# Sensor_Board_0x08_Dual_Temperatures_2xDS.net
KiCad netlist of a schematic drawn in EAGLE
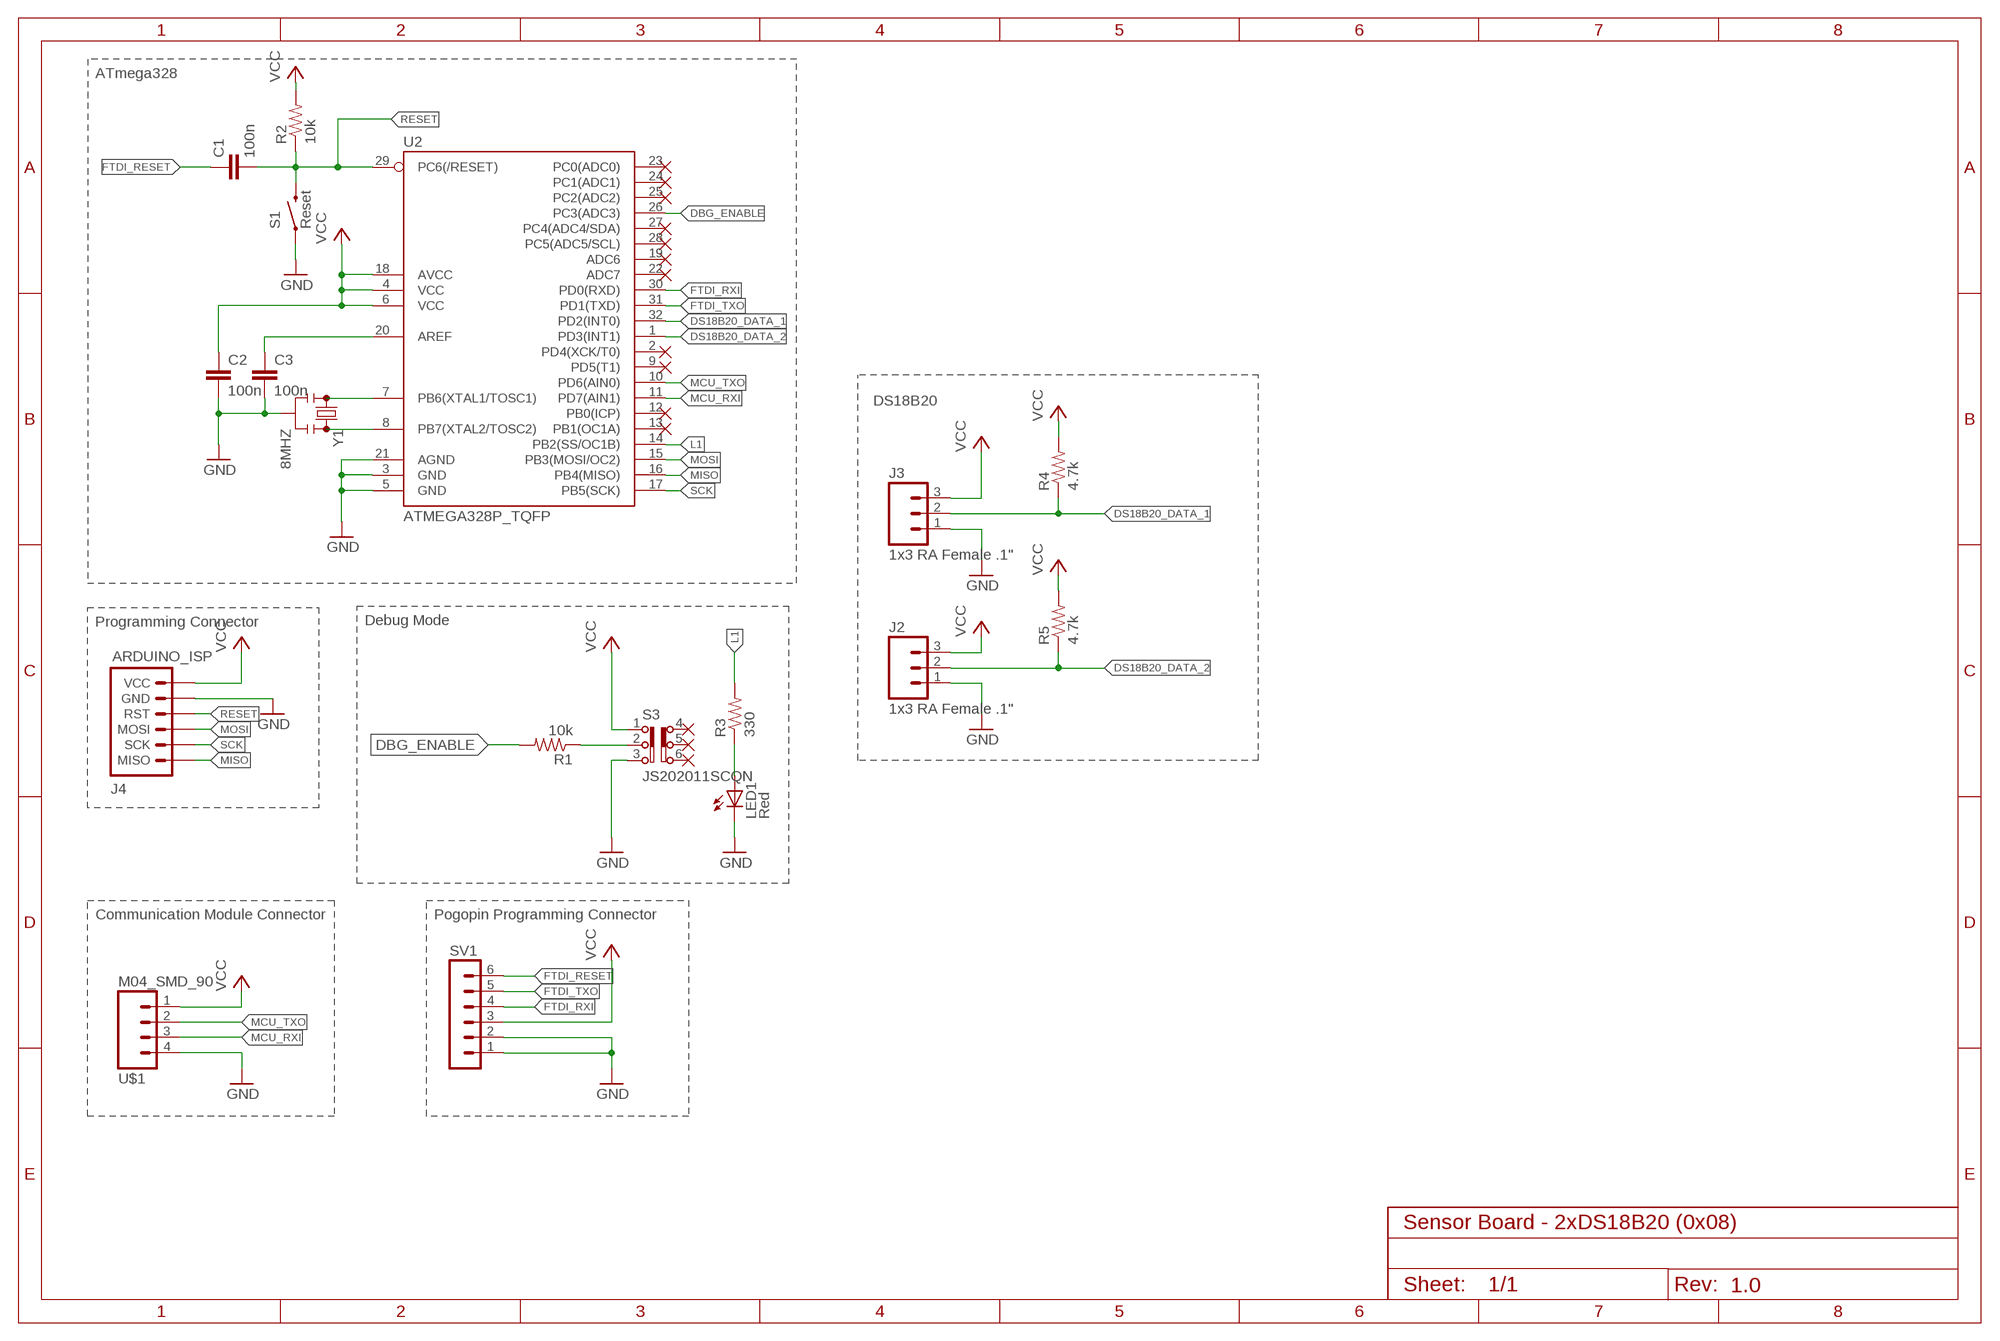
[diagram p0: schematic, sheet 1]

(export (version "E")
  (design (tool "Eeschema 10.0.6"))
  (components
    (comp (ref "C1")
      (value "100n")
      (footprint "eagle-import:C0805")
      (libsource (lib "eagle-import") (part "C"))
    )
    (comp (ref "C2")
      (value "100n")
      (footprint "eagle-import:C0805")
      (libsource (lib "eagle-import") (part "C"))
    )
    (comp (ref "C3")
      (value "100n")
      (footprint "eagle-import:C0805")
      (libsource (lib "eagle-import") (part "C"))
    )
    (comp (ref "J2")
      (value "1x3 RA Female .1\"")
      (footprint "eagle-import:1X03_SMD_RA_FEMALE")
      (libsource (lib "eagle-import") (part "M03SMD_RA_FEMALE"))
    )
    (comp (ref "J3")
      (value "1x3 RA Female .1\"")
      (footprint "eagle-import:1X03_SMD_RA_FEMALE")
      (libsource (lib "eagle-import") (part "M03SMD_RA_FEMALE"))
    )
    (comp (ref "J4")
      (value "ARDUINO_ISP")
      (footprint "eagle-import:M-2X3")
      (libsource (lib "eagle-import") (part "ARDUINO_ISP"))
    )
    (comp (ref "LED1")
      (value "Red")
      (footprint "eagle-import:SML0805")
      (libsource (lib "eagle-import") (part "LEDSML0805"))
    )
    (comp (ref "R1")
      (value "10k")
      (footprint "eagle-import:0805")
      (libsource (lib "eagle-import") (part "RESISTOR0805-RES"))
    )
    (comp (ref "R2")
      (value "10k")
      (footprint "eagle-import:0805")
      (libsource (lib "eagle-import") (part "RESISTOR0805-RES"))
    )
    (comp (ref "R3")
      (value "330")
      (footprint "eagle-import:0805")
      (libsource (lib "eagle-import") (part "RESISTOR0805-RES"))
    )
    (comp (ref "R4")
      (value "4.7k")
      (footprint "eagle-import:0805")
      (libsource (lib "eagle-import") (part "RESISTOR0805-RES"))
    )
    (comp (ref "R5")
      (value "4.7k")
      (footprint "eagle-import:0805")
      (libsource (lib "eagle-import") (part "RESISTOR0805-RES"))
    )
    (comp (ref "S1")
      (value "Reset")
      (footprint "eagle-import:M-PUSHBUTTON-SMD")
      (libsource (lib "eagle-import") (part "PUSHBUTTON"))
    )
    (comp (ref "S3")
      (value "JS202011SCQN")
      (footprint "eagle-import:JS202011SCQN")
      (libsource (lib "eagle-import") (part "JS202011SCQN"))
    )
    (comp (ref "SV1")
      (value "MA06-1")
      (footprint "eagle-import:MA06-1")
      (libsource (lib "eagle-import") (part "MA06-1"))
    )
    (comp (ref "U$1")
      (value "M04_SMD_90")
      (footprint "eagle-import:M04_SMD_90")
      (libsource (lib "eagle-import") (part "M04_SMD_90"))
    )
    (comp (ref "U2")
      (value "ATMEGA328P_TQFP")
      (footprint "eagle-import:TQFP32-08")
      (libsource (lib "eagle-import") (part "ATMEGA328P_TQFP"))
    )
    (comp (ref "Y1")
      (value "8MHZ")
      (footprint "eagle-import:RESONATOR-SMD")
      (libsource (lib "eagle-import") (part "RESONATOR8MHZ"))
    )
  )
  (nets
    (net (code "1") (name "DBG_ENABLE") (class "Default")
      (node (ref "R1") (pin "2") (pinfunction "2_2") (pintype "passive"))
      (node (ref "U2") (pin "26") (pinfunction "PC3(ADC3)_26") (pintype "bidirectional"))
    )
    (net (code "2") (name "DS18B20_DATA_1") (class "Default")
      (node (ref "J3") (pin "2") (pinfunction "2_2") (pintype "passive"))
      (node (ref "R4") (pin "1") (pinfunction "1_1") (pintype "passive"))
      (node (ref "U2") (pin "32") (pinfunction "PD2(INT0)_32") (pintype "bidirectional"))
    )
    (net (code "3") (name "DS18B20_DATA_2") (class "Default")
      (node (ref "J2") (pin "2") (pinfunction "2_2") (pintype "passive"))
      (node (ref "R5") (pin "1") (pinfunction "1_1") (pintype "passive"))
      (node (ref "U2") (pin "1") (pinfunction "PD3(INT1)_1") (pintype "bidirectional"))
    )
    (net (code "4") (name "FTDI_RESET") (class "Default")
      (node (ref "C1") (pin "1") (pinfunction "1_1") (pintype "passive"))
      (node (ref "SV1") (pin "6") (pinfunction "6_6") (pintype "passive"))
    )
    (net (code "5") (name "FTDI_RXI") (class "Default")
      (node (ref "SV1") (pin "4") (pinfunction "4_4") (pintype "passive"))
      (node (ref "U2") (pin "30") (pinfunction "PD0(RXD)_30") (pintype "bidirectional"))
    )
    (net (code "6") (name "FTDI_TXO") (class "Default")
      (node (ref "SV1") (pin "5") (pinfunction "5_5") (pintype "passive"))
      (node (ref "U2") (pin "31") (pinfunction "PD1(TXD)_31") (pintype "bidirectional"))
    )
    (net (code "7") (name "GND") (class "Default")
      (node (ref "C2") (pin "2") (pinfunction "2_2") (pintype "passive"))
      (node (ref "C3") (pin "2") (pinfunction "2_2") (pintype "passive"))
      (node (ref "J2") (pin "1") (pinfunction "1_1") (pintype "passive"))
      (node (ref "J3") (pin "1") (pinfunction "1_1") (pintype "passive"))
      (node (ref "J4") (pin "P$5") (pinfunction "GND_P$5") (pintype "passive"))
      (node (ref "LED1") (pin "C") (pinfunction "C_C") (pintype "passive"))
      (node (ref "S1") (pin "1") (pinfunction "LEFT_1") (pintype "passive"))
      (node (ref "S1") (pin "2") (pinfunction "LEFT_2") (pintype "passive"))
      (node (ref "S3") (pin "3") (pinfunction "3_3") (pintype "passive"))
      (node (ref "SV1") (pin "1") (pinfunction "1_1") (pintype "passive"))
      (node (ref "SV1") (pin "2") (pinfunction "2_2") (pintype "passive"))
      (node (ref "U$1") (pin "4") (pinfunction "4_4") (pintype "passive"))
      (node (ref "U2") (pin "21") (pinfunction "AGND_21") (pintype "bidirectional"))
      (node (ref "U2") (pin "3") (pinfunction "GND_3") (pintype "bidirectional"))
      (node (ref "U2") (pin "5") (pinfunction "GND_5") (pintype "bidirectional"))
      (node (ref "Y1") (pin "2") (pinfunction "2_2") (pintype "passive"))
    )
    (net (code "8") (name "L1") (class "Default")
      (node (ref "R3") (pin "2") (pinfunction "2_2") (pintype "passive"))
      (node (ref "U2") (pin "14") (pinfunction "PB2(SS/OC1B)_14") (pintype "bidirectional"))
    )
    (net (code "9") (name "MCU_RXI") (class "Default")
      (node (ref "U$1") (pin "3") (pinfunction "3_3") (pintype "passive"))
      (node (ref "U2") (pin "11") (pinfunction "PD7(AIN1)_11") (pintype "bidirectional"))
    )
    (net (code "10") (name "MCU_TXO") (class "Default")
      (node (ref "U$1") (pin "2") (pinfunction "2_2") (pintype "passive"))
      (node (ref "U2") (pin "10") (pinfunction "PD6(AIN0)_10") (pintype "bidirectional"))
    )
    (net (code "11") (name "MISO") (class "Default")
      (node (ref "J4") (pin "P$1") (pinfunction "MISO_P$1") (pintype "passive"))
      (node (ref "U2") (pin "16") (pinfunction "PB4(MISO)_16") (pintype "bidirectional"))
    )
    (net (code "12") (name "MOSI") (class "Default")
      (node (ref "J4") (pin "P$3") (pinfunction "MOSI_P$3") (pintype "passive"))
      (node (ref "U2") (pin "15") (pinfunction "PB3(MOSI/OC2)_15") (pintype "bidirectional"))
    )
    (net (code "13") (name "Net-(LED1-PadA)") (class "Default")
      (node (ref "LED1") (pin "A") (pinfunction "A_A") (pintype "passive"))
      (node (ref "R3") (pin "1") (pinfunction "1_1") (pintype "passive"))
    )
    (net (code "14") (name "Net-(R1-Pad1)") (class "Default")
      (node (ref "R1") (pin "1") (pinfunction "1_1") (pintype "passive"))
      (node (ref "S3") (pin "2") (pinfunction "2_2") (pintype "passive"))
    )
    (net (code "15") (name "Net-(U2-AREF)") (class "Default")
      (node (ref "C3") (pin "1") (pinfunction "1_1") (pintype "passive"))
      (node (ref "U2") (pin "20") (pinfunction "AREF_20") (pintype "bidirectional"))
    )
    (net (code "16") (name "Net-(U2-PB6(XTAL1{slash}TOSC1))") (class "Default")
      (node (ref "U2") (pin "7") (pinfunction "PB6(XTAL1/TOSC1)_7") (pintype "bidirectional"))
      (node (ref "Y1") (pin "1") (pinfunction "1_1") (pintype "passive"))
    )
    (net (code "17") (name "Net-(U2-PB7(XTAL2{slash}TOSC2))") (class "Default")
      (node (ref "U2") (pin "8") (pinfunction "PB7(XTAL2/TOSC2)_8") (pintype "bidirectional"))
      (node (ref "Y1") (pin "3") (pinfunction "3_3") (pintype "passive"))
    )
    (net (code "18") (name "RESET") (class "Default")
      (node (ref "C1") (pin "2") (pinfunction "2_2") (pintype "passive"))
      (node (ref "J4") (pin "P$4") (pinfunction "RST_P$4") (pintype "passive"))
      (node (ref "R2") (pin "1") (pinfunction "1_1") (pintype "passive"))
      (node (ref "S1") (pin "3") (pinfunction "RIGHT_3") (pintype "passive"))
      (node (ref "S1") (pin "4") (pinfunction "RIGHT_4") (pintype "passive"))
      (node (ref "U2") (pin "29") (pinfunction "PC6(/RESET)_29") (pintype "bidirectional"))
    )
    (net (code "19") (name "SCK") (class "Default")
      (node (ref "J4") (pin "P$2") (pinfunction "SCK_P$2") (pintype "passive"))
      (node (ref "U2") (pin "17") (pinfunction "PB5(SCK)_17") (pintype "bidirectional"))
    )
    (net (code "20") (name "VCC") (class "Default")
      (node (ref "C2") (pin "1") (pinfunction "1_1") (pintype "passive"))
      (node (ref "J2") (pin "3") (pinfunction "3_3") (pintype "passive"))
      (node (ref "J3") (pin "3") (pinfunction "3_3") (pintype "passive"))
      (node (ref "J4") (pin "P$6") (pinfunction "VCC_P$6") (pintype "passive"))
      (node (ref "R2") (pin "2") (pinfunction "2_2") (pintype "passive"))
      (node (ref "R4") (pin "2") (pinfunction "2_2") (pintype "passive"))
      (node (ref "R5") (pin "2") (pinfunction "2_2") (pintype "passive"))
      (node (ref "S3") (pin "1") (pinfunction "1_1") (pintype "passive"))
      (node (ref "SV1") (pin "3") (pinfunction "3_3") (pintype "passive"))
      (node (ref "U$1") (pin "1") (pinfunction "1_1") (pintype "passive"))
      (node (ref "U2") (pin "18") (pinfunction "AVCC_18") (pintype "bidirectional"))
      (node (ref "U2") (pin "4") (pinfunction "VCC_4") (pintype "bidirectional"))
      (node (ref "U2") (pin "6") (pinfunction "VCC_6") (pintype "bidirectional"))
    )
    (net (code "21") (name "unconnected-(S3-Pad4)") (class "Default")
      (node (ref "S3") (pin "4") (pinfunction "4_4") (pintype "passive"))
    )
    (net (code "22") (name "unconnected-(S3-Pad5)") (class "Default")
      (node (ref "S3") (pin "5") (pinfunction "5_5") (pintype "passive"))
    )
    (net (code "23") (name "unconnected-(S3-Pad6)") (class "Default")
      (node (ref "S3") (pin "6") (pinfunction "6_6") (pintype "passive"))
    )
    (net (code "24") (name "unconnected-(U2-ADC6-Pad19)") (class "Default")
      (node (ref "U2") (pin "19") (pinfunction "ADC6_19") (pintype "bidirectional"))
    )
    (net (code "25") (name "unconnected-(U2-ADC7-Pad22)") (class "Default")
      (node (ref "U2") (pin "22") (pinfunction "ADC7_22") (pintype "bidirectional"))
    )
    (net (code "26") (name "unconnected-(U2-PB0(ICP)-Pad12)") (class "Default")
      (node (ref "U2") (pin "12") (pinfunction "PB0(ICP)_12") (pintype "bidirectional"))
    )
    (net (code "27") (name "unconnected-(U2-PB1(OC1A)-Pad13)") (class "Default")
      (node (ref "U2") (pin "13") (pinfunction "PB1(OC1A)_13") (pintype "bidirectional"))
    )
    (net (code "28") (name "unconnected-(U2-PC0(ADC0)-Pad23)") (class "Default")
      (node (ref "U2") (pin "23") (pinfunction "PC0(ADC0)_23") (pintype "bidirectional"))
    )
    (net (code "29") (name "unconnected-(U2-PC1(ADC1)-Pad24)") (class "Default")
      (node (ref "U2") (pin "24") (pinfunction "PC1(ADC1)_24") (pintype "bidirectional"))
    )
    (net (code "30") (name "unconnected-(U2-PC2(ADC2)-Pad25)") (class "Default")
      (node (ref "U2") (pin "25") (pinfunction "PC2(ADC2)_25") (pintype "bidirectional"))
    )
    (net (code "31") (name "unconnected-(U2-PC4(ADC4{slash}SDA)-Pad27)") (class "Default")
      (node (ref "U2") (pin "27") (pinfunction "PC4(ADC4/SDA)_27") (pintype "bidirectional"))
    )
    (net (code "32") (name "unconnected-(U2-PC5(ADC5{slash}SCL)-Pad28)") (class "Default")
      (node (ref "U2") (pin "28") (pinfunction "PC5(ADC5/SCL)_28") (pintype "bidirectional"))
    )
    (net (code "33") (name "unconnected-(U2-PD4(XCK{slash}T0)-Pad2)") (class "Default")
      (node (ref "U2") (pin "2") (pinfunction "PD4(XCK/T0)_2") (pintype "bidirectional"))
    )
    (net (code "34") (name "unconnected-(U2-PD5(T1)-Pad9)") (class "Default")
      (node (ref "U2") (pin "9") (pinfunction "PD5(T1)_9") (pintype "bidirectional"))
    )
  )
)
